# noritz-controller.net
KiCad netlist of a schematic drawn in EasyEDA
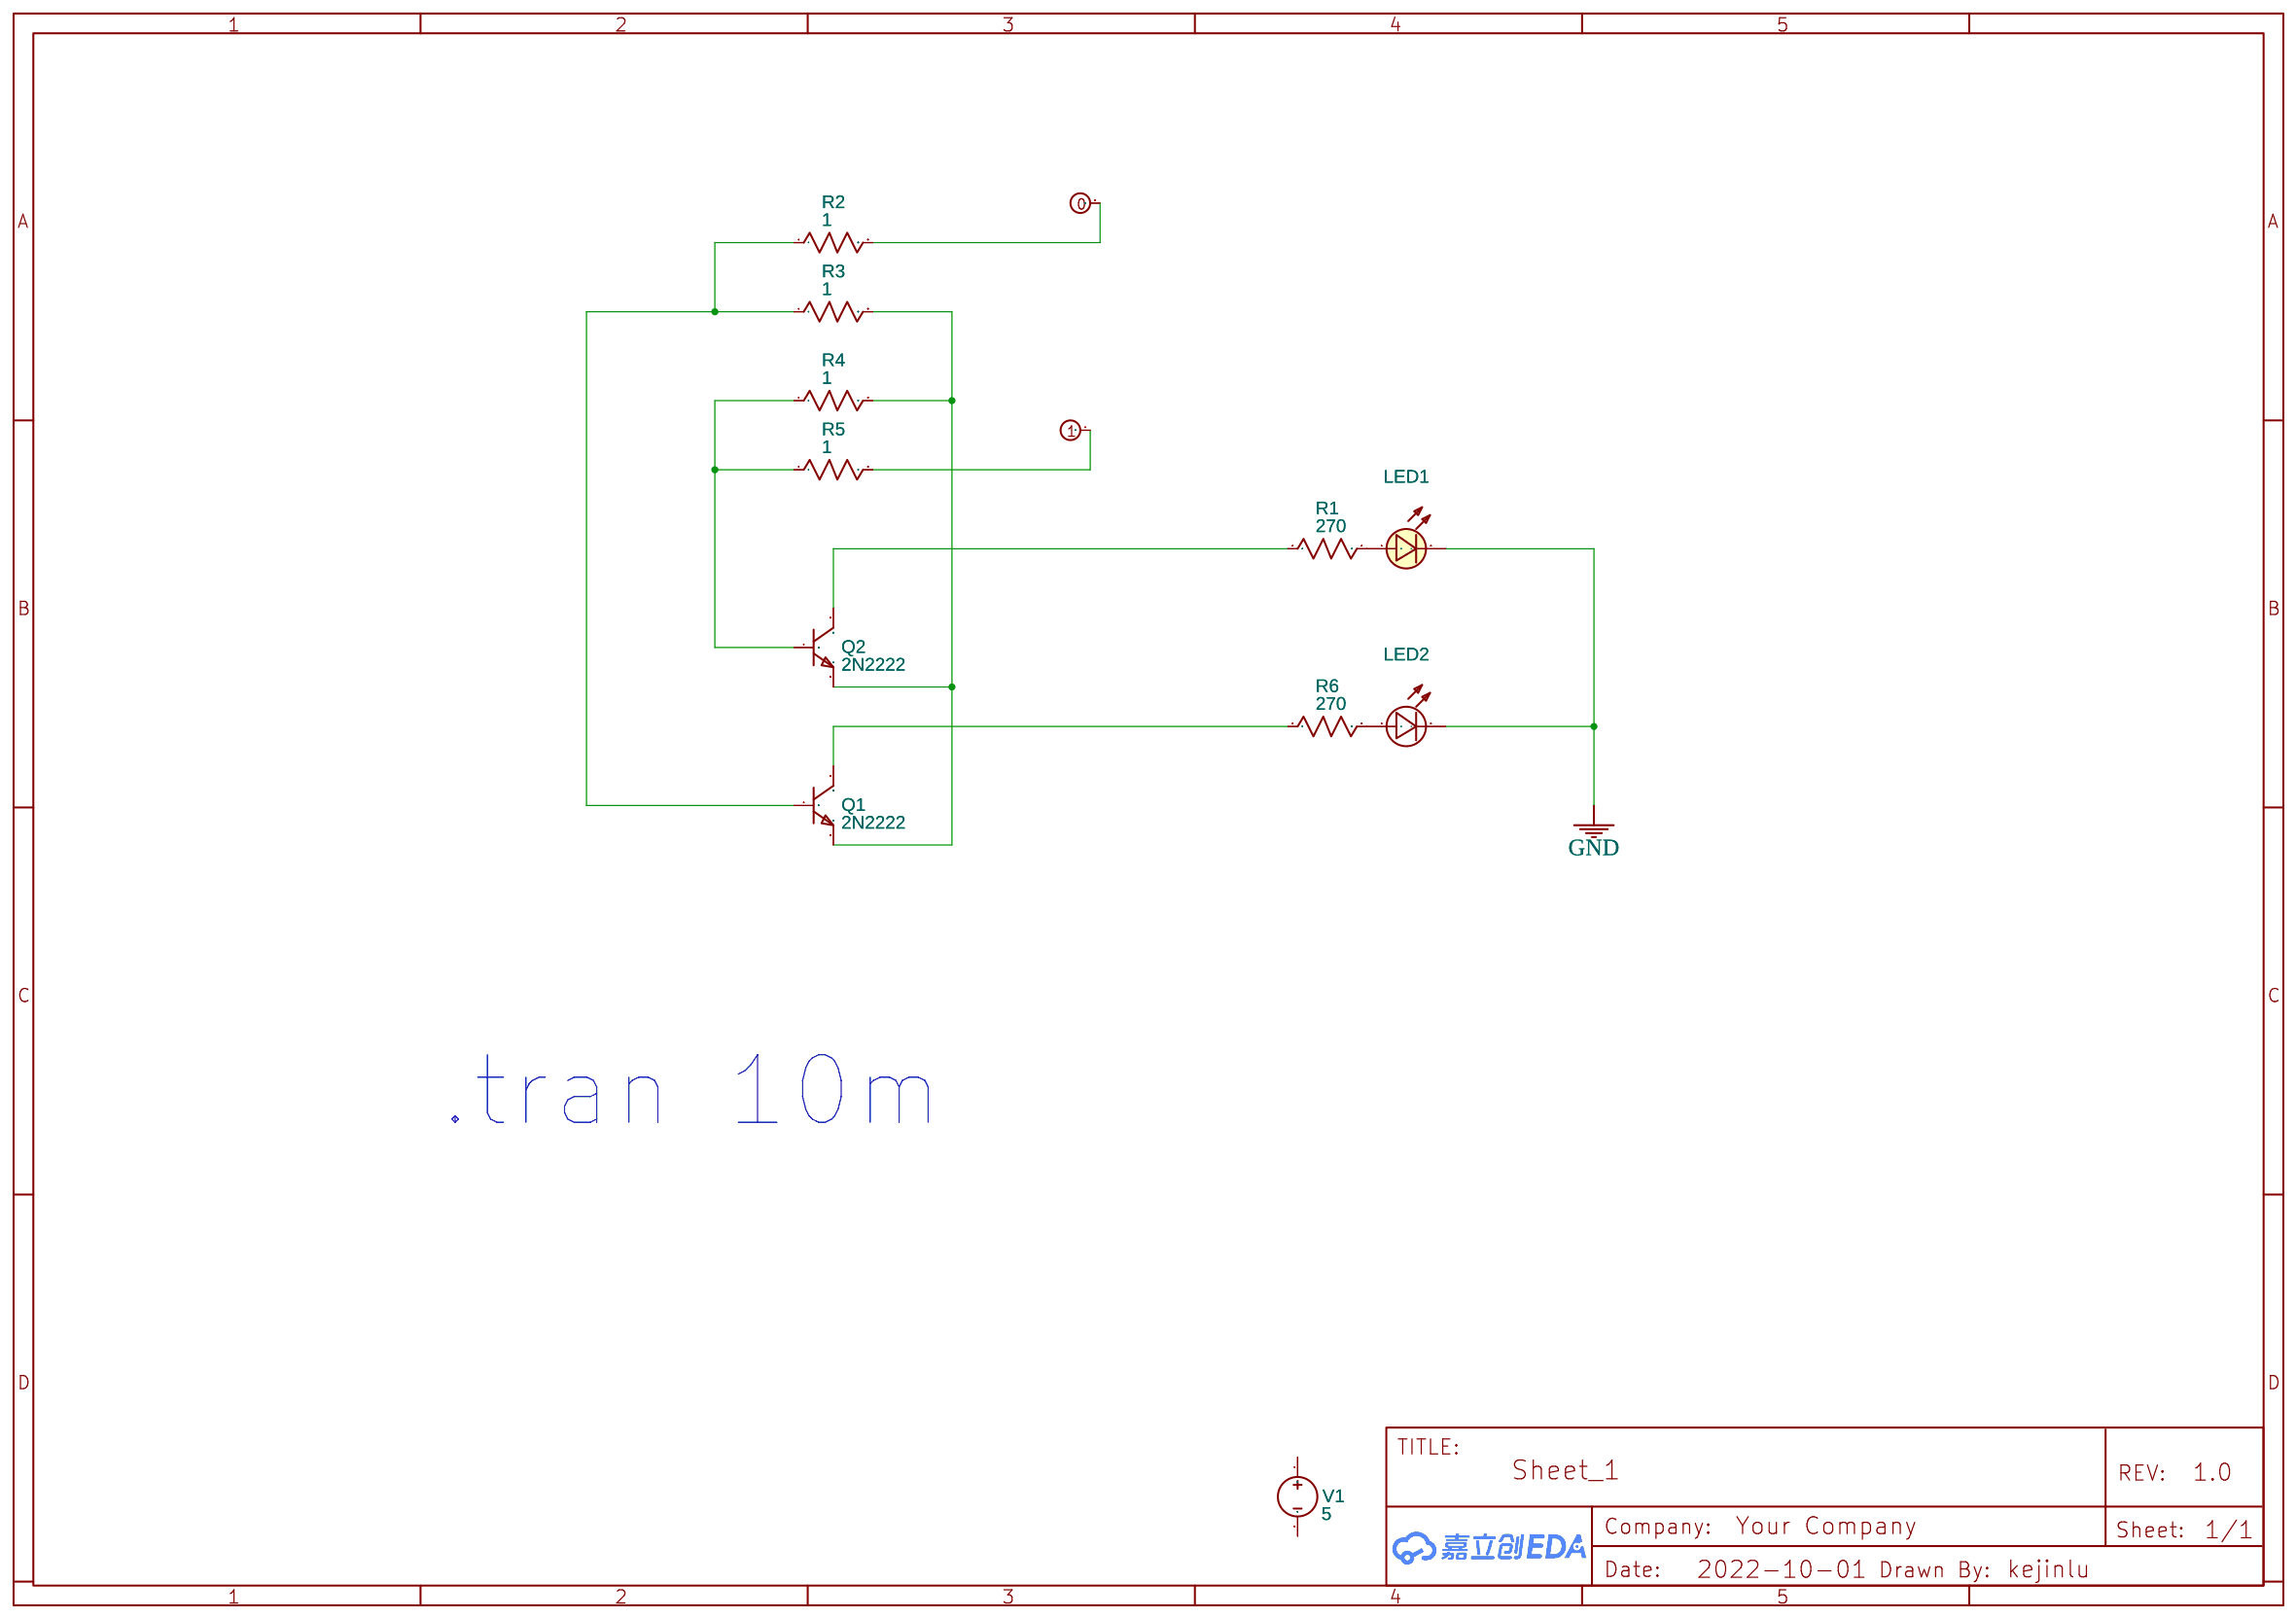
[diagram p0: 三极管功能验证]
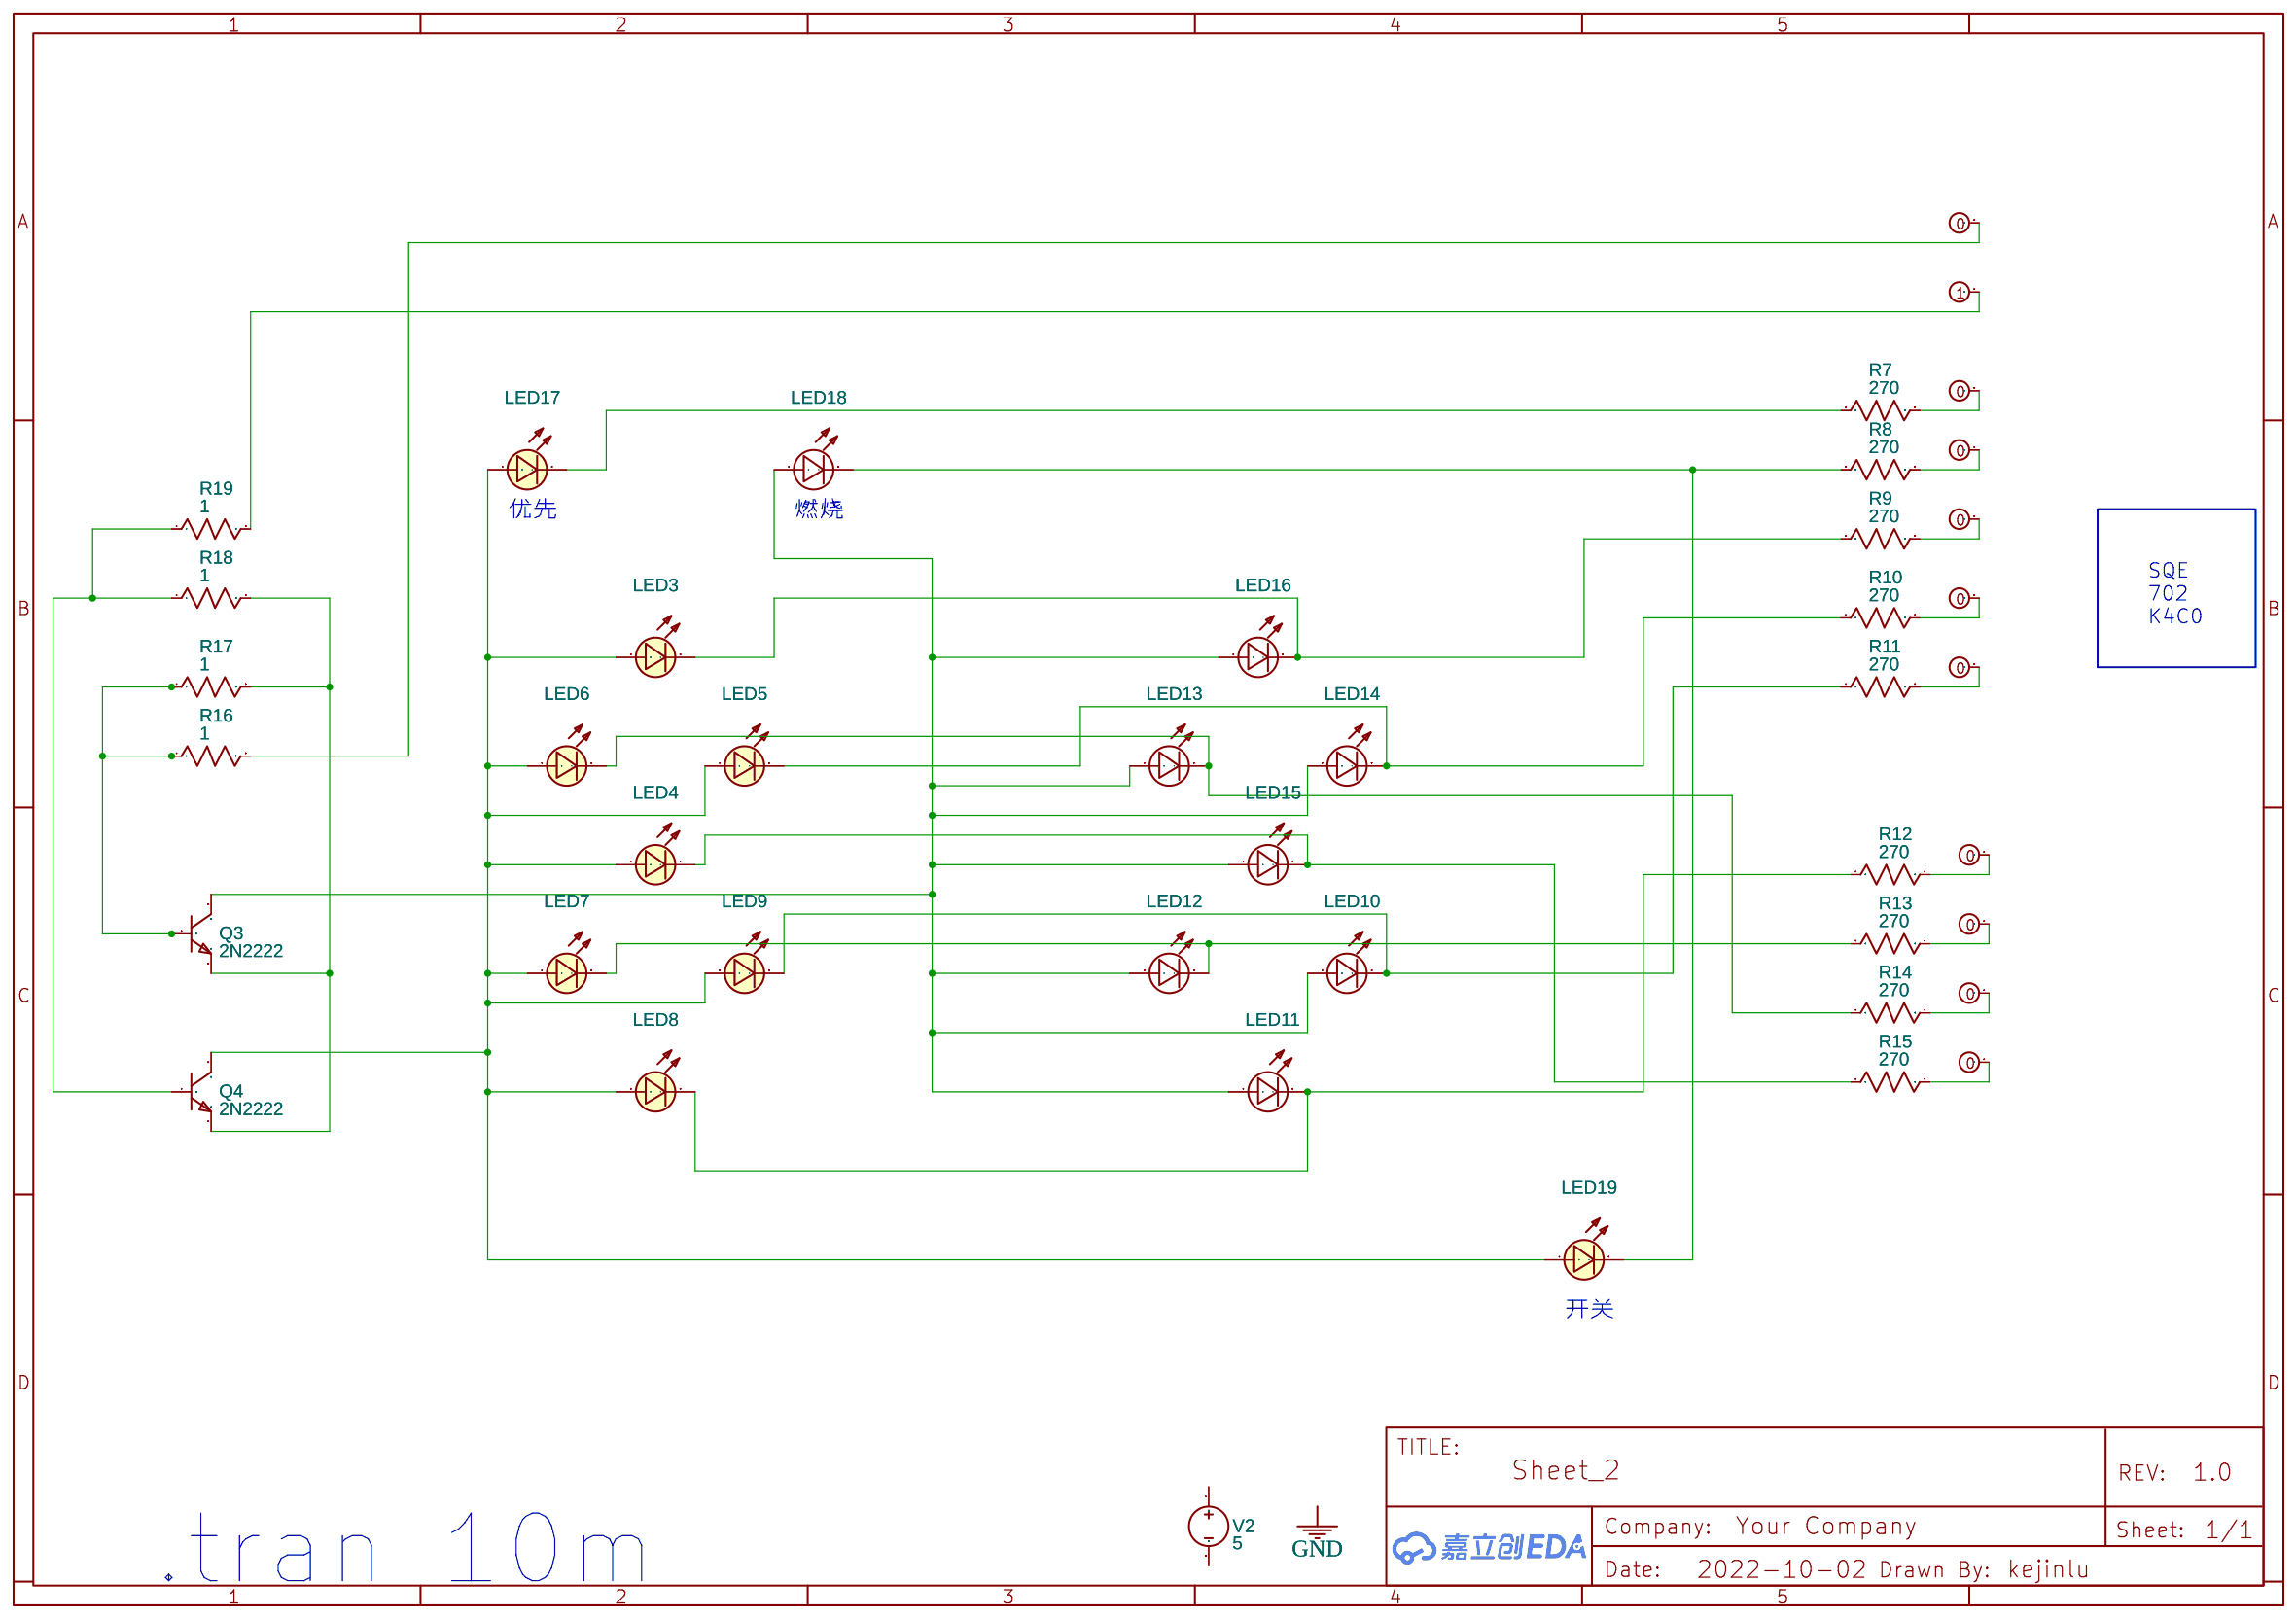
[diagram p1: 线控LED电路]
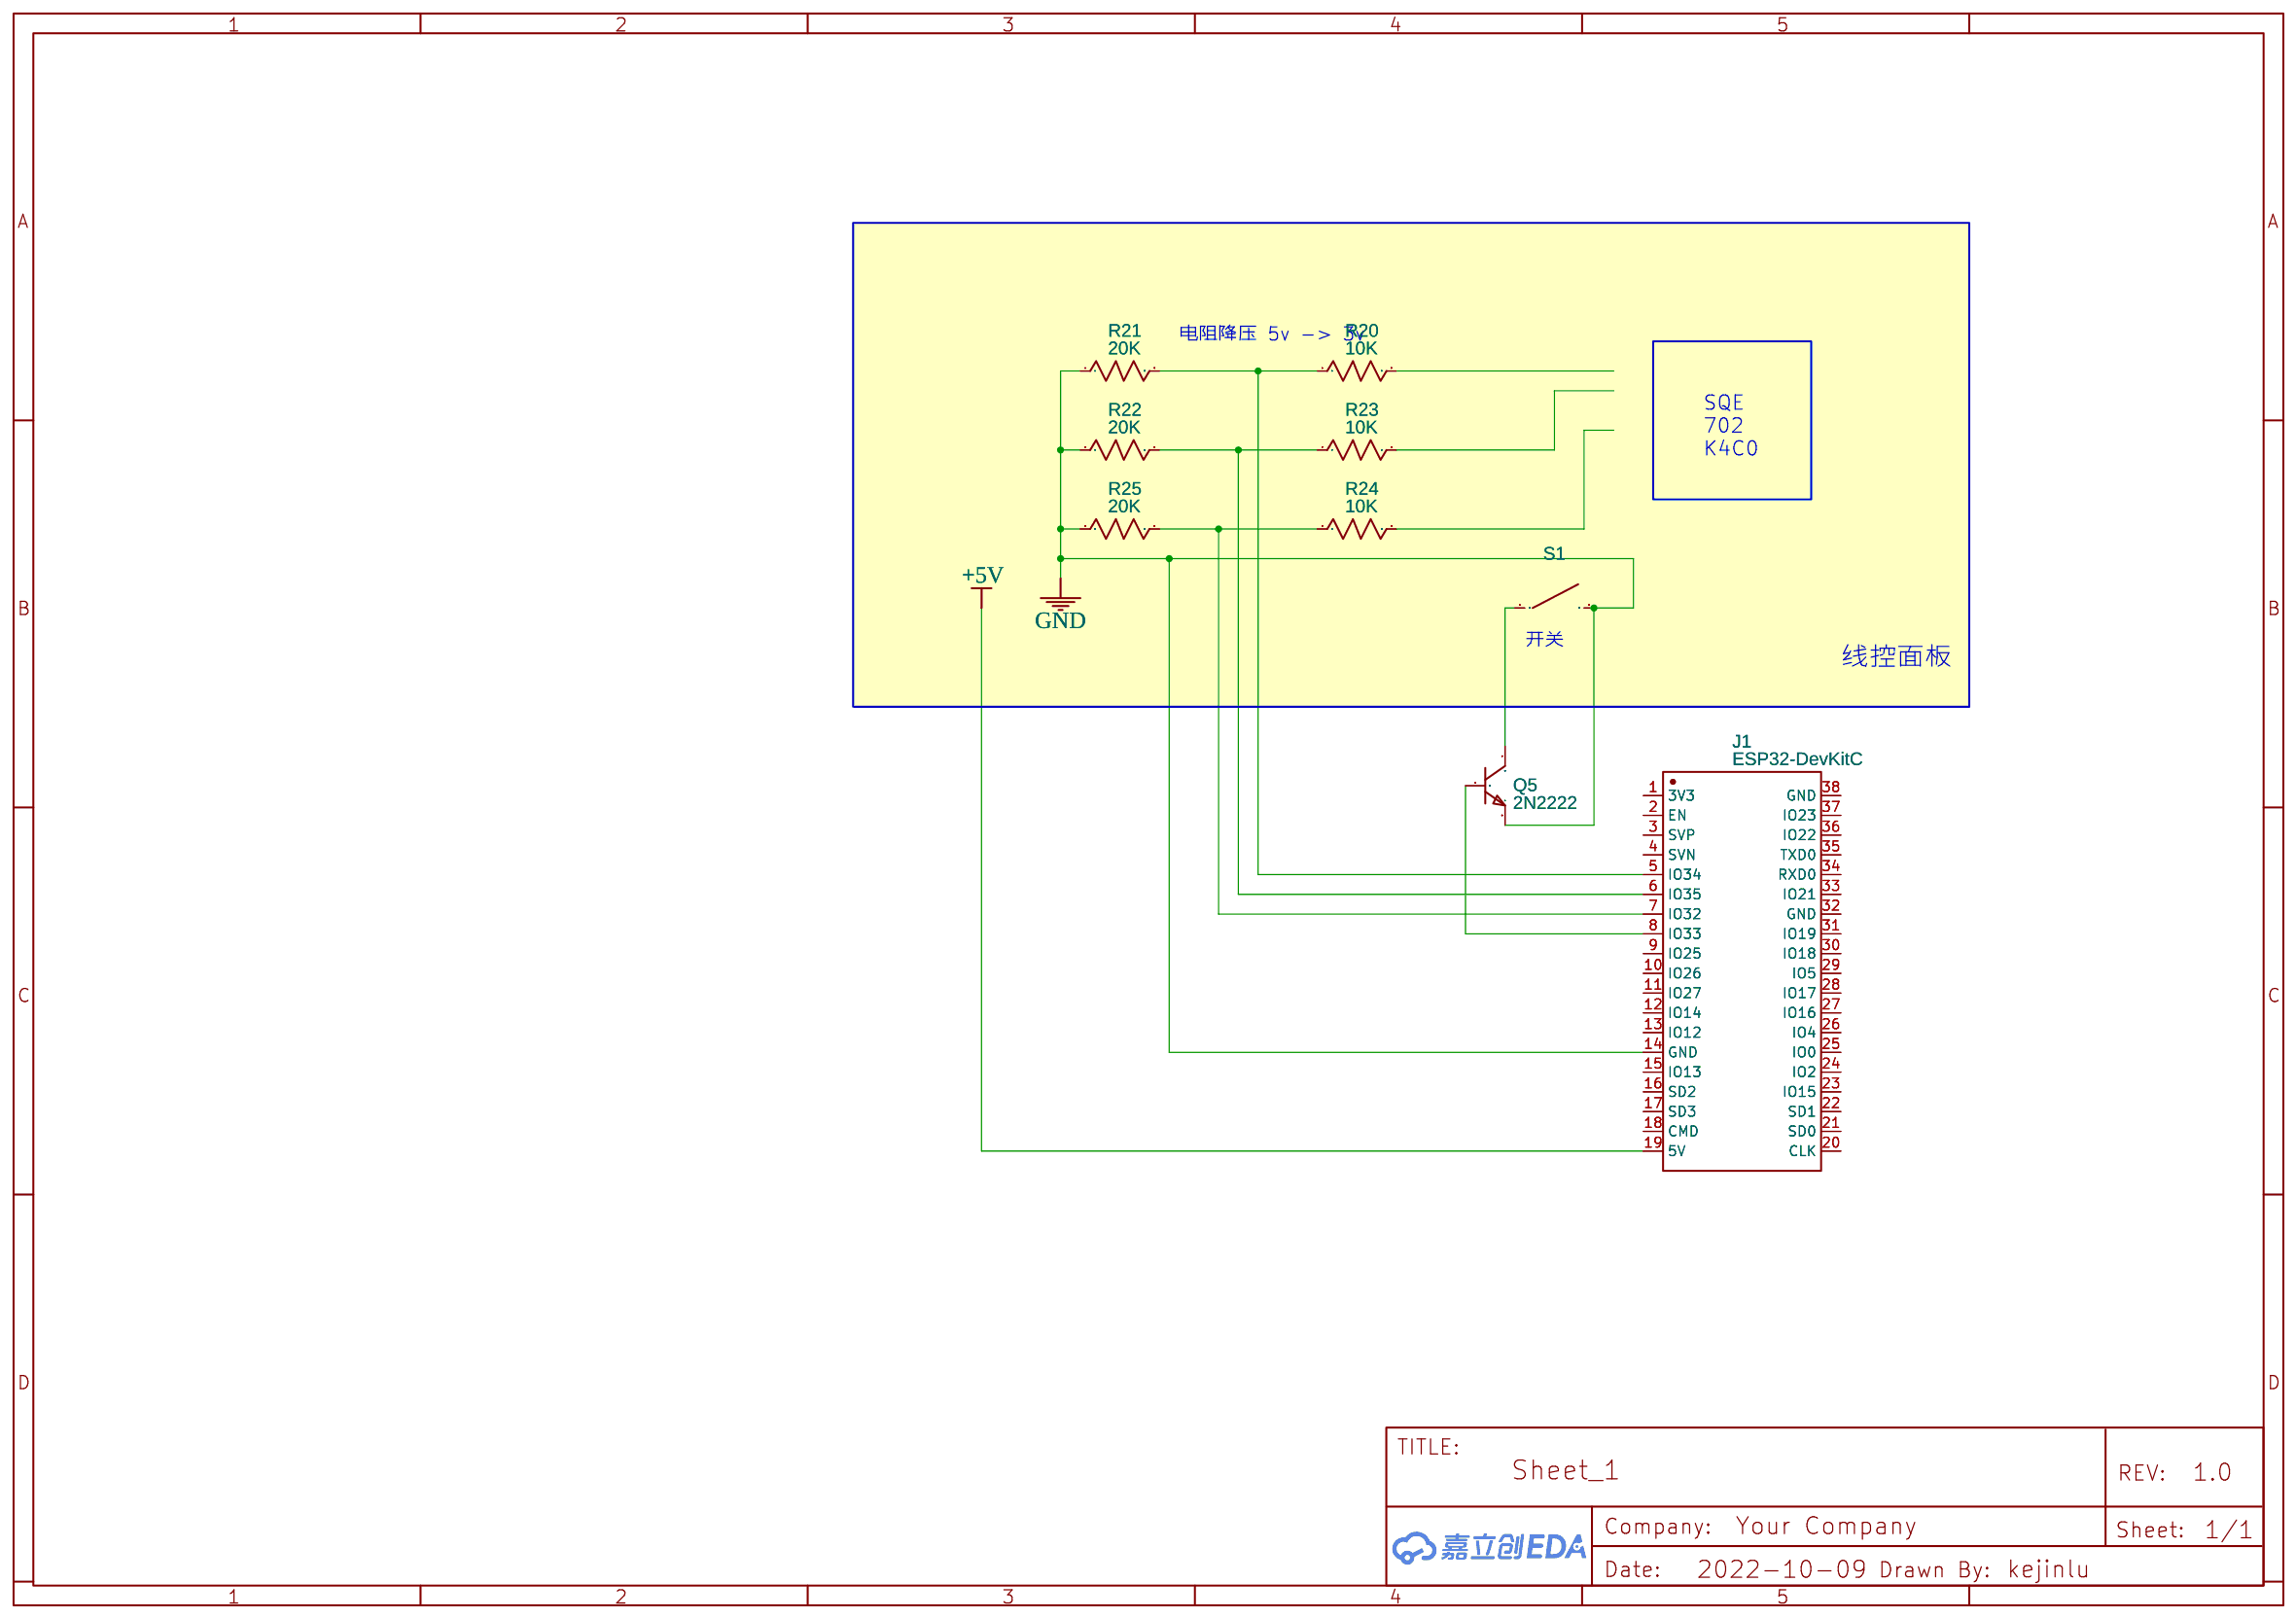
[diagram p2: ESP32接线]

(export (version "E")
  (design (tool "Eeschema 10.0.6"))
  (components
    (comp (ref "LED1") (value "LED") (libsource (lib "") (part "LED")))
    (comp (ref "LED2") (value "LED") (libsource (lib "") (part "LED_1")))
    (comp (ref "Q1") (value "2N2222") (libsource (lib "") (part "2N2222")))
    (comp (ref "Q2") (value "2N2222") (libsource (lib "") (part "2N2222")))
    (comp (ref "R1") (value "270") (libsource (lib "") (part "Resistor_US")))
    (comp (ref "R2") (value "1") (libsource (lib "") (part "Resistor_US")))
    (comp (ref "R3") (value "1") (libsource (lib "") (part "Resistor_US")))
    (comp (ref "R4") (value "1") (libsource (lib "") (part "Resistor_US")))
    (comp (ref "R5") (value "1") (libsource (lib "") (part "Resistor_US")))
    (comp (ref "R6") (value "270") (libsource (lib "") (part "Resistor_US")))
    (comp (ref "U1") (value "Logicstate1") (libsource (lib "") (part "LOGICSTATE")))
    (comp (ref "U2") (value "Logicstate1") (libsource (lib "") (part "LOGICSTATE_1")))
    (comp (ref "V1") (value "5") (libsource (lib "") (part "VDC")))
    (comp (ref "LED3") (value "LED") (libsource (lib "") (part "LED")))
    (comp (ref "LED4") (value "LED") (libsource (lib "") (part "LED")))
    (comp (ref "LED5") (value "LED") (libsource (lib "") (part "LED")))
    (comp (ref "LED6") (value "LED") (libsource (lib "") (part "LED")))
    (comp (ref "LED7") (value "LED") (libsource (lib "") (part "LED")))
    (comp (ref "LED8") (value "LED") (libsource (lib "") (part "LED")))
    (comp (ref "LED9") (value "LED") (libsource (lib "") (part "LED")))
    (comp (ref "LED10") (value "LED") (libsource (lib "") (part "LED_1")))
    (comp (ref "LED11") (value "LED") (libsource (lib "") (part "LED_1")))
    (comp (ref "LED12") (value "LED") (libsource (lib "") (part "LED_1")))
    (comp (ref "LED13") (value "LED") (libsource (lib "") (part "LED_1")))
    (comp (ref "LED14") (value "LED") (libsource (lib "") (part "LED_1")))
    (comp (ref "LED15") (value "LED") (libsource (lib "") (part "LED_1")))
    (comp (ref "LED16") (value "LED") (libsource (lib "") (part "LED_1")))
    (comp (ref "LED17") (value "LED") (libsource (lib "") (part "LED")))
    (comp (ref "LED18") (value "LED") (libsource (lib "") (part "LED_1")))
    (comp (ref "LED19") (value "LED") (libsource (lib "") (part "LED")))
    (comp (ref "Q3") (value "2N2222") (libsource (lib "") (part "2N2222")))
    (comp (ref "Q4") (value "2N2222") (libsource (lib "") (part "2N2222")))
    (comp (ref "R7") (value "270") (libsource (lib "") (part "Resistor_US")))
    (comp (ref "R8") (value "270") (libsource (lib "") (part "Resistor_US")))
    (comp (ref "R9") (value "270") (libsource (lib "") (part "Resistor_US")))
    (comp (ref "R10") (value "270") (libsource (lib "") (part "Resistor_US")))
    (comp (ref "R11") (value "270") (libsource (lib "") (part "Resistor_US")))
    (comp (ref "R12") (value "270") (libsource (lib "") (part "Resistor_US")))
    (comp (ref "R13") (value "270") (libsource (lib "") (part "Resistor_US")))
    (comp (ref "R14") (value "270") (libsource (lib "") (part "Resistor_US")))
    (comp (ref "R15") (value "270") (libsource (lib "") (part "Resistor_US")))
    (comp (ref "R16") (value "1") (libsource (lib "") (part "Resistor_US")))
    (comp (ref "R17") (value "1") (libsource (lib "") (part "Resistor_US")))
    (comp (ref "R18") (value "1") (libsource (lib "") (part "Resistor_US")))
    (comp (ref "R19") (value "1") (libsource (lib "") (part "Resistor_US")))
    (comp (ref "U3") (value "Logicstate1") (libsource (lib "") (part "LOGICSTATE")))
    (comp (ref "U4") (value "Logicstate1") (libsource (lib "") (part "LOGICSTATE_1")))
    (comp (ref "U5") (value "Logicstate1") (libsource (lib "") (part "LOGICSTATE")))
    (comp (ref "U6") (value "Logicstate1") (libsource (lib "") (part "LOGICSTATE")))
    (comp (ref "U7") (value "Logicstate1") (libsource (lib "") (part "LOGICSTATE")))
    (comp (ref "U8") (value "Logicstate1") (libsource (lib "") (part "LOGICSTATE")))
    (comp (ref "U9") (value "Logicstate1") (libsource (lib "") (part "LOGICSTATE")))
    (comp (ref "U10") (value "Logicstate1") (libsource (lib "") (part "LOGICSTATE")))
    (comp (ref "U11") (value "Logicstate1") (libsource (lib "") (part "LOGICSTATE")))
    (comp (ref "U12") (value "Logicstate1") (libsource (lib "") (part "LOGICSTATE")))
    (comp (ref "U13") (value "Logicstate1") (libsource (lib "") (part "LOGICSTATE")))
    (comp (ref "V2") (value "5") (libsource (lib "") (part "VDC")))
    (comp (ref "J1") (value "ESP32-DevKitC") (libsource (lib "") (part "ESP32-DevKitC")))
    (comp (ref "Q5") (value "2N2222") (libsource (lib "") (part "2N2222")))
    (comp (ref "R20") (value "10K") (libsource (lib "") (part "Resistor_US")))
    (comp (ref "R21") (value "20K") (libsource (lib "") (part "Resistor_US")))
    (comp (ref "R22") (value "20K") (libsource (lib "") (part "Resistor_US")))
    (comp (ref "R23") (value "10K") (libsource (lib "") (part "Resistor_US")))
    (comp (ref "R24") (value "10K") (libsource (lib "") (part "Resistor_US")))
    (comp (ref "R25") (value "20K") (libsource (lib "") (part "Resistor_US")))
    (comp (ref "S1") (value "SPST_Open") (libsource (lib "") (part "SPST")))
  )
  (nets
    (net (code "1") (name "+5V") (class "Default")
      (node (ref "J1") (pin "19") (pinfunction "5V_19") (pintype "unspecified"))
    )
    (net (code "2") (name "GND") (class "Default")
      (node (ref "J1") (pin "14") (pinfunction "GND_14") (pintype "unspecified"))
      (node (ref "LED1") (pin "2") (pinfunction "-_2") (pintype "unspecified"))
      (node (ref "LED2") (pin "2") (pinfunction "-_2") (pintype "unspecified"))
      (node (ref "Q5") (pin "2") (pinfunction "E_2") (pintype "unspecified"))
      (node (ref "R21") (pin "1") (pinfunction "1_1") (pintype "unspecified"))
      (node (ref "R22") (pin "1") (pinfunction "1_1") (pintype "unspecified"))
      (node (ref "R25") (pin "1") (pinfunction "1_1") (pintype "unspecified"))
      (node (ref "S1") (pin "2") (pinfunction "2_2") (pintype "unspecified"))
    )
    (net (code "3") (name "Net-(J1-IO32)") (class "Default")
      (node (ref "J1") (pin "7") (pinfunction "IO32_7") (pintype "unspecified"))
      (node (ref "R24") (pin "1") (pinfunction "1_1") (pintype "unspecified"))
      (node (ref "R25") (pin "2") (pinfunction "2_2") (pintype "unspecified"))
    )
    (net (code "4") (name "Net-(J1-IO33)") (class "Default")
      (node (ref "J1") (pin "8") (pinfunction "IO33_8") (pintype "unspecified"))
      (node (ref "Q5") (pin "1") (pinfunction "B_1") (pintype "unspecified"))
    )
    (net (code "5") (name "Net-(J1-IO34)") (class "Default")
      (node (ref "J1") (pin "5") (pinfunction "IO34_5") (pintype "unspecified"))
      (node (ref "R20") (pin "1") (pinfunction "1_1") (pintype "unspecified"))
      (node (ref "R21") (pin "2") (pinfunction "2_2") (pintype "unspecified"))
    )
    (net (code "6") (name "Net-(J1-IO35)") (class "Default")
      (node (ref "J1") (pin "6") (pinfunction "IO35_6") (pintype "unspecified"))
      (node (ref "R22") (pin "2") (pinfunction "2_2") (pintype "unspecified"))
      (node (ref "R23") (pin "1") (pinfunction "1_1") (pintype "unspecified"))
    )
    (net (code "7") (name "Net-(LED1-+)") (class "Default")
      (node (ref "LED1") (pin "1") (pinfunction "+_1") (pintype "unspecified"))
      (node (ref "R1") (pin "2") (pinfunction "2_2") (pintype "unspecified"))
    )
    (net (code "8") (name "Net-(LED2-+)") (class "Default")
      (node (ref "LED2") (pin "1") (pinfunction "+_1") (pintype "unspecified"))
      (node (ref "R6") (pin "2") (pinfunction "2_2") (pintype "unspecified"))
    )
    (net (code "9") (name "Net-(LED10-+)") (class "Default")
      (node (ref "LED10") (pin "1") (pinfunction "+_1") (pintype "unspecified"))
      (node (ref "LED11") (pin "1") (pinfunction "+_1") (pintype "unspecified"))
      (node (ref "LED12") (pin "1") (pinfunction "+_1") (pintype "unspecified"))
      (node (ref "LED13") (pin "1") (pinfunction "+_1") (pintype "unspecified"))
      (node (ref "LED14") (pin "1") (pinfunction "+_1") (pintype "unspecified"))
      (node (ref "LED15") (pin "1") (pinfunction "+_1") (pintype "unspecified"))
      (node (ref "LED16") (pin "1") (pinfunction "+_1") (pintype "unspecified"))
      (node (ref "LED18") (pin "1") (pinfunction "+_1") (pintype "unspecified"))
      (node (ref "Q3") (pin "3") (pinfunction "C_3") (pintype "unspecified"))
    )
    (net (code "10") (name "Net-(LED10--)") (class "Default")
      (node (ref "LED10") (pin "2") (pinfunction "-_2") (pintype "unspecified"))
      (node (ref "LED9") (pin "2") (pinfunction "-_2") (pintype "unspecified"))
      (node (ref "R11") (pin "1") (pinfunction "1_1") (pintype "unspecified"))
    )
    (net (code "11") (name "Net-(LED11--)") (class "Default")
      (node (ref "LED11") (pin "2") (pinfunction "-_2") (pintype "unspecified"))
      (node (ref "LED8") (pin "2") (pinfunction "-_2") (pintype "unspecified"))
      (node (ref "R12") (pin "1") (pinfunction "1_1") (pintype "unspecified"))
    )
    (net (code "12") (name "Net-(LED12--)") (class "Default")
      (node (ref "LED12") (pin "2") (pinfunction "-_2") (pintype "unspecified"))
      (node (ref "LED7") (pin "2") (pinfunction "-_2") (pintype "unspecified"))
      (node (ref "R13") (pin "1") (pinfunction "1_1") (pintype "unspecified"))
    )
    (net (code "13") (name "Net-(LED13--)") (class "Default")
      (node (ref "LED13") (pin "2") (pinfunction "-_2") (pintype "unspecified"))
      (node (ref "LED6") (pin "2") (pinfunction "-_2") (pintype "unspecified"))
      (node (ref "R14") (pin "1") (pinfunction "1_1") (pintype "unspecified"))
    )
    (net (code "14") (name "Net-(LED14--)") (class "Default")
      (node (ref "LED14") (pin "2") (pinfunction "-_2") (pintype "unspecified"))
      (node (ref "LED5") (pin "2") (pinfunction "-_2") (pintype "unspecified"))
      (node (ref "R10") (pin "1") (pinfunction "1_1") (pintype "unspecified"))
    )
    (net (code "15") (name "Net-(LED15--)") (class "Default")
      (node (ref "LED15") (pin "2") (pinfunction "-_2") (pintype "unspecified"))
      (node (ref "LED4") (pin "2") (pinfunction "-_2") (pintype "unspecified"))
      (node (ref "R15") (pin "1") (pinfunction "1_1") (pintype "unspecified"))
    )
    (net (code "16") (name "Net-(LED16--)") (class "Default")
      (node (ref "LED16") (pin "2") (pinfunction "-_2") (pintype "unspecified"))
      (node (ref "LED3") (pin "2") (pinfunction "-_2") (pintype "unspecified"))
      (node (ref "R9") (pin "1") (pinfunction "1_1") (pintype "unspecified"))
    )
    (net (code "17") (name "Net-(LED17-+)") (class "Default")
      (node (ref "LED17") (pin "1") (pinfunction "+_1") (pintype "unspecified"))
      (node (ref "LED19") (pin "1") (pinfunction "+_1") (pintype "unspecified"))
      (node (ref "LED3") (pin "1") (pinfunction "+_1") (pintype "unspecified"))
      (node (ref "LED4") (pin "1") (pinfunction "+_1") (pintype "unspecified"))
      (node (ref "LED5") (pin "1") (pinfunction "+_1") (pintype "unspecified"))
      (node (ref "LED6") (pin "1") (pinfunction "+_1") (pintype "unspecified"))
      (node (ref "LED7") (pin "1") (pinfunction "+_1") (pintype "unspecified"))
      (node (ref "LED8") (pin "1") (pinfunction "+_1") (pintype "unspecified"))
      (node (ref "LED9") (pin "1") (pinfunction "+_1") (pintype "unspecified"))
      (node (ref "Q4") (pin "3") (pinfunction "C_3") (pintype "unspecified"))
    )
    (net (code "18") (name "Net-(LED17--)") (class "Default")
      (node (ref "LED17") (pin "2") (pinfunction "-_2") (pintype "unspecified"))
      (node (ref "R7") (pin "1") (pinfunction "1_1") (pintype "unspecified"))
    )
    (net (code "19") (name "Net-(LED18--)") (class "Default")
      (node (ref "LED18") (pin "2") (pinfunction "-_2") (pintype "unspecified"))
      (node (ref "LED19") (pin "2") (pinfunction "-_2") (pintype "unspecified"))
      (node (ref "R8") (pin "1") (pinfunction "1_1") (pintype "unspecified"))
    )
    (net (code "20") (name "Net-(Q1-B)") (class "Default")
      (node (ref "Q1") (pin "1") (pinfunction "B_1") (pintype "unspecified"))
      (node (ref "R2") (pin "1") (pinfunction "1_1") (pintype "unspecified"))
      (node (ref "R3") (pin "1") (pinfunction "1_1") (pintype "unspecified"))
    )
    (net (code "21") (name "Net-(Q1-C)") (class "Default")
      (node (ref "Q1") (pin "3") (pinfunction "C_3") (pintype "unspecified"))
      (node (ref "R6") (pin "1") (pinfunction "1_1") (pintype "unspecified"))
    )
    (net (code "22") (name "Net-(Q1-E)") (class "Default")
      (node (ref "Q1") (pin "2") (pinfunction "E_2") (pintype "unspecified"))
      (node (ref "Q2") (pin "2") (pinfunction "E_2") (pintype "unspecified"))
      (node (ref "R3") (pin "2") (pinfunction "2_2") (pintype "unspecified"))
      (node (ref "R4") (pin "2") (pinfunction "2_2") (pintype "unspecified"))
    )
    (net (code "23") (name "Net-(Q2-B)") (class "Default")
      (node (ref "Q2") (pin "1") (pinfunction "B_1") (pintype "unspecified"))
      (node (ref "R4") (pin "1") (pinfunction "1_1") (pintype "unspecified"))
      (node (ref "R5") (pin "1") (pinfunction "1_1") (pintype "unspecified"))
    )
    (net (code "24") (name "Net-(Q2-C)") (class "Default")
      (node (ref "Q2") (pin "3") (pinfunction "C_3") (pintype "unspecified"))
      (node (ref "R1") (pin "1") (pinfunction "1_1") (pintype "unspecified"))
    )
    (net (code "25") (name "Net-(Q3-B)") (class "Default")
      (node (ref "Q3") (pin "1") (pinfunction "B_1") (pintype "unspecified"))
      (node (ref "R16") (pin "1") (pinfunction "1_1") (pintype "unspecified"))
      (node (ref "R17") (pin "1") (pinfunction "1_1") (pintype "unspecified"))
    )
    (net (code "26") (name "Net-(Q3-E)") (class "Default")
      (node (ref "Q3") (pin "2") (pinfunction "E_2") (pintype "unspecified"))
      (node (ref "Q4") (pin "2") (pinfunction "E_2") (pintype "unspecified"))
      (node (ref "R17") (pin "2") (pinfunction "2_2") (pintype "unspecified"))
      (node (ref "R18") (pin "2") (pinfunction "2_2") (pintype "unspecified"))
    )
    (net (code "27") (name "Net-(Q4-B)") (class "Default")
      (node (ref "Q4") (pin "1") (pinfunction "B_1") (pintype "unspecified"))
      (node (ref "R18") (pin "1") (pinfunction "1_1") (pintype "unspecified"))
      (node (ref "R19") (pin "1") (pinfunction "1_1") (pintype "unspecified"))
    )
    (net (code "28") (name "Net-(Q5-C)") (class "Default")
      (node (ref "Q5") (pin "3") (pinfunction "C_3") (pintype "unspecified"))
      (node (ref "S1") (pin "1") (pinfunction "1_1") (pintype "unspecified"))
    )
    (net (code "29") (name "Net-(R2-Pad2)") (class "Default")
      (node (ref "R2") (pin "2") (pinfunction "2_2") (pintype "unspecified"))
      (node (ref "U1") (pin "1") (pinfunction "1_1") (pintype "unspecified"))
    )
    (net (code "30") (name "Net-(R5-Pad2)") (class "Default")
      (node (ref "R5") (pin "2") (pinfunction "2_2") (pintype "unspecified"))
      (node (ref "U2") (pin "1") (pinfunction "1_1") (pintype "unspecified"))
    )
    (net (code "31") (name "Net-(R7-Pad2)") (class "Default")
      (node (ref "R7") (pin "2") (pinfunction "2_2") (pintype "unspecified"))
      (node (ref "U5") (pin "1") (pinfunction "1_1") (pintype "unspecified"))
    )
    (net (code "32") (name "Net-(R8-Pad2)") (class "Default")
      (node (ref "R8") (pin "2") (pinfunction "2_2") (pintype "unspecified"))
      (node (ref "U6") (pin "1") (pinfunction "1_1") (pintype "unspecified"))
    )
    (net (code "33") (name "Net-(R9-Pad2)") (class "Default")
      (node (ref "R9") (pin "2") (pinfunction "2_2") (pintype "unspecified"))
      (node (ref "U7") (pin "1") (pinfunction "1_1") (pintype "unspecified"))
    )
    (net (code "34") (name "Net-(R10-Pad2)") (class "Default")
      (node (ref "R10") (pin "2") (pinfunction "2_2") (pintype "unspecified"))
      (node (ref "U8") (pin "1") (pinfunction "1_1") (pintype "unspecified"))
    )
    (net (code "35") (name "Net-(R11-Pad2)") (class "Default")
      (node (ref "R11") (pin "2") (pinfunction "2_2") (pintype "unspecified"))
      (node (ref "U9") (pin "1") (pinfunction "1_1") (pintype "unspecified"))
    )
    (net (code "36") (name "Net-(R12-Pad2)") (class "Default")
      (node (ref "R12") (pin "2") (pinfunction "2_2") (pintype "unspecified"))
      (node (ref "U10") (pin "1") (pinfunction "1_1") (pintype "unspecified"))
    )
    (net (code "37") (name "Net-(R13-Pad2)") (class "Default")
      (node (ref "R13") (pin "2") (pinfunction "2_2") (pintype "unspecified"))
      (node (ref "U11") (pin "1") (pinfunction "1_1") (pintype "unspecified"))
    )
    (net (code "38") (name "Net-(R14-Pad2)") (class "Default")
      (node (ref "R14") (pin "2") (pinfunction "2_2") (pintype "unspecified"))
      (node (ref "U12") (pin "1") (pinfunction "1_1") (pintype "unspecified"))
    )
    (net (code "39") (name "Net-(R15-Pad2)") (class "Default")
      (node (ref "R15") (pin "2") (pinfunction "2_2") (pintype "unspecified"))
      (node (ref "U13") (pin "1") (pinfunction "1_1") (pintype "unspecified"))
    )
    (net (code "40") (name "Net-(R16-Pad2)") (class "Default")
      (node (ref "R16") (pin "2") (pinfunction "2_2") (pintype "unspecified"))
      (node (ref "U3") (pin "1") (pinfunction "1_1") (pintype "unspecified"))
    )
    (net (code "41") (name "Net-(R19-Pad2)") (class "Default")
      (node (ref "R19") (pin "2") (pinfunction "2_2") (pintype "unspecified"))
      (node (ref "U4") (pin "1") (pinfunction "1_1") (pintype "unspecified"))
    )
    (net (code "42") (name "unconnected-(J1-3V3-Pad1)") (class "Default")
      (node (ref "J1") (pin "1") (pinfunction "3V3_1") (pintype "unspecified"))
    )
    (net (code "43") (name "unconnected-(J1-CLK-Pad20)") (class "Default")
      (node (ref "J1") (pin "20") (pinfunction "CLK_20") (pintype "unspecified"))
    )
    (net (code "44") (name "unconnected-(J1-CMD-Pad18)") (class "Default")
      (node (ref "J1") (pin "18") (pinfunction "CMD_18") (pintype "unspecified"))
    )
    (net (code "45") (name "unconnected-(J1-EN-Pad2)") (class "Default")
      (node (ref "J1") (pin "2") (pinfunction "EN_2") (pintype "unspecified"))
    )
    (net (code "46") (name "unconnected-(J1-GND-Pad32)") (class "Default")
      (node (ref "J1") (pin "32") (pinfunction "GND_32") (pintype "unspecified"))
    )
    (net (code "47") (name "unconnected-(J1-GND-Pad38)") (class "Default")
      (node (ref "J1") (pin "38") (pinfunction "GND_38") (pintype "unspecified"))
    )
    (net (code "48") (name "unconnected-(J1-IO0-Pad25)") (class "Default")
      (node (ref "J1") (pin "25") (pinfunction "IO0_25") (pintype "unspecified"))
    )
    (net (code "49") (name "unconnected-(J1-IO2-Pad24)") (class "Default")
      (node (ref "J1") (pin "24") (pinfunction "IO2_24") (pintype "unspecified"))
    )
    (net (code "50") (name "unconnected-(J1-IO4-Pad26)") (class "Default")
      (node (ref "J1") (pin "26") (pinfunction "IO4_26") (pintype "unspecified"))
    )
    (net (code "51") (name "unconnected-(J1-IO5-Pad29)") (class "Default")
      (node (ref "J1") (pin "29") (pinfunction "IO5_29") (pintype "unspecified"))
    )
    (net (code "52") (name "unconnected-(J1-IO12-Pad13)") (class "Default")
      (node (ref "J1") (pin "13") (pinfunction "IO12_13") (pintype "unspecified"))
    )
    (net (code "53") (name "unconnected-(J1-IO13-Pad15)") (class "Default")
      (node (ref "J1") (pin "15") (pinfunction "IO13_15") (pintype "unspecified"))
    )
    (net (code "54") (name "unconnected-(J1-IO14-Pad12)") (class "Default")
      (node (ref "J1") (pin "12") (pinfunction "IO14_12") (pintype "unspecified"))
    )
    (net (code "55") (name "unconnected-(J1-IO15-Pad23)") (class "Default")
      (node (ref "J1") (pin "23") (pinfunction "IO15_23") (pintype "unspecified"))
    )
    (net (code "56") (name "unconnected-(J1-IO16-Pad27)") (class "Default")
      (node (ref "J1") (pin "27") (pinfunction "IO16_27") (pintype "unspecified"))
    )
    (net (code "57") (name "unconnected-(J1-IO17-Pad28)") (class "Default")
      (node (ref "J1") (pin "28") (pinfunction "IO17_28") (pintype "unspecified"))
    )
    (net (code "58") (name "unconnected-(J1-IO18-Pad30)") (class "Default")
      (node (ref "J1") (pin "30") (pinfunction "IO18_30") (pintype "unspecified"))
    )
    (net (code "59") (name "unconnected-(J1-IO19-Pad31)") (class "Default")
      (node (ref "J1") (pin "31") (pinfunction "IO19_31") (pintype "unspecified"))
    )
    (net (code "60") (name "unconnected-(J1-IO21-Pad33)") (class "Default")
      (node (ref "J1") (pin "33") (pinfunction "IO21_33") (pintype "unspecified"))
    )
    (net (code "61") (name "unconnected-(J1-IO22-Pad36)") (class "Default")
      (node (ref "J1") (pin "36") (pinfunction "IO22_36") (pintype "unspecified"))
    )
    (net (code "62") (name "unconnected-(J1-IO23-Pad37)") (class "Default")
      (node (ref "J1") (pin "37") (pinfunction "IO23_37") (pintype "unspecified"))
    )
    (net (code "63") (name "unconnected-(J1-IO25-Pad9)") (class "Default")
      (node (ref "J1") (pin "9") (pinfunction "IO25_9") (pintype "unspecified"))
    )
    (net (code "64") (name "unconnected-(J1-IO26-Pad10)") (class "Default")
      (node (ref "J1") (pin "10") (pinfunction "IO26_10") (pintype "unspecified"))
    )
    (net (code "65") (name "unconnected-(J1-IO27-Pad11)") (class "Default")
      (node (ref "J1") (pin "11") (pinfunction "IO27_11") (pintype "unspecified"))
    )
    (net (code "66") (name "unconnected-(J1-RXD0-Pad34)") (class "Default")
      (node (ref "J1") (pin "34") (pinfunction "RXD0_34") (pintype "unspecified"))
    )
    (net (code "67") (name "unconnected-(J1-SD0-Pad21)") (class "Default")
      (node (ref "J1") (pin "21") (pinfunction "SD0_21") (pintype "unspecified"))
    )
    (net (code "68") (name "unconnected-(J1-SD1-Pad22)") (class "Default")
      (node (ref "J1") (pin "22") (pinfunction "SD1_22") (pintype "unspecified"))
    )
    (net (code "69") (name "unconnected-(J1-SD2-Pad16)") (class "Default")
      (node (ref "J1") (pin "16") (pinfunction "SD2_16") (pintype "unspecified"))
    )
    (net (code "70") (name "unconnected-(J1-SD3-Pad17)") (class "Default")
      (node (ref "J1") (pin "17") (pinfunction "SD3_17") (pintype "unspecified"))
    )
    (net (code "71") (name "unconnected-(J1-SVN-Pad4)") (class "Default")
      (node (ref "J1") (pin "4") (pinfunction "SVN_4") (pintype "unspecified"))
    )
    (net (code "72") (name "unconnected-(J1-SVP-Pad3)") (class "Default")
      (node (ref "J1") (pin "3") (pinfunction "SVP_3") (pintype "unspecified"))
    )
    (net (code "73") (name "unconnected-(J1-TXD0-Pad35)") (class "Default")
      (node (ref "J1") (pin "35") (pinfunction "TXD0_35") (pintype "unspecified"))
    )
    (net (code "74") (name "unconnected-(R20-Pad2)") (class "Default")
      (node (ref "R20") (pin "2") (pinfunction "2_2") (pintype "unspecified"))
    )
    (net (code "75") (name "unconnected-(R23-Pad2)") (class "Default")
      (node (ref "R23") (pin "2") (pinfunction "2_2") (pintype "unspecified"))
    )
    (net (code "76") (name "unconnected-(R24-Pad2)") (class "Default")
      (node (ref "R24") (pin "2") (pinfunction "2_2") (pintype "unspecified"))
    )
    (net (code "77") (name "unconnected-(V1-Pad1)") (class "Default")
      (node (ref "V1") (pin "1") (pinfunction "1_1") (pintype "unspecified"))
    )
    (net (code "78") (name "unconnected-(V1-Pad2)") (class "Default")
      (node (ref "V1") (pin "2") (pinfunction "2_2") (pintype "unspecified"))
    )
    (net (code "79") (name "unconnected-(V2-Pad1)") (class "Default")
      (node (ref "V2") (pin "1") (pinfunction "1_1") (pintype "unspecified"))
    )
    (net (code "80") (name "unconnected-(V2-Pad2)") (class "Default")
      (node (ref "V2") (pin "2") (pinfunction "2_2") (pintype "unspecified"))
    )
  )
)
